# XL_N76E003K2__MAIN.net
KiCad netlist of a schematic drawn in Altium Designer
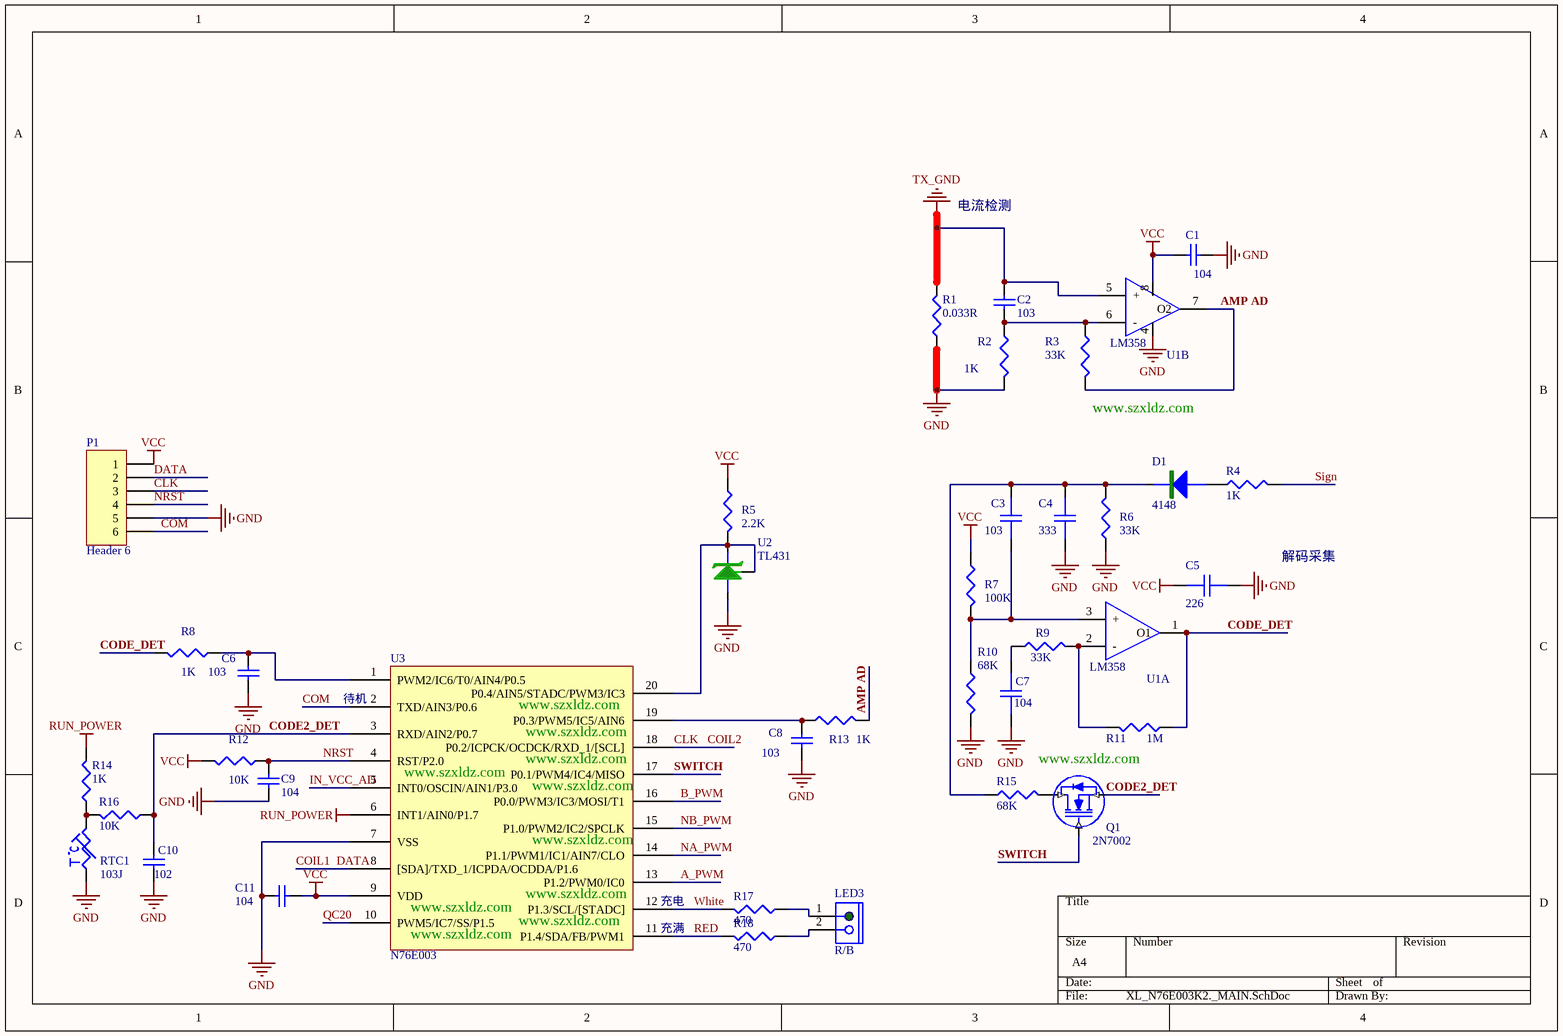
[diagram p0: XL_N76E003K2._MAIN.SchDoc]

(export (version "E")
  (design (tool "Eeschema 10.0.6"))
  (components
    (comp (ref "C1")
      (value "104")
      (footprint "C0402")
      (description "Capacitor")
      (fields (field (name "PUBLISHER") "Altium Limited"))
      (libsource (lib "*") (part "Cap"))
    )
    (comp (ref "C2")
      (value "103")
      (footprint "C0402")
      (description "Capacitor")
      (fields (field (name "PUBLISHER") "Altium Limited"))
      (libsource (lib "*") (part "Cap"))
    )
    (comp (ref "C3") (value "103") (footprint "C0402") (libsource (lib "*") (part "CH")))
    (comp (ref "C4") (value "333") (footprint "C0402") (libsource (lib "*") (part "CH")))
    (comp (ref "C5") (value "226") (footprint "C0805") (libsource (lib "*") (part "CH")))
    (comp (ref "C6")
      (value "103")
      (footprint "C0402")
      (description "Capacitor")
      (fields (field (name "PUBLISHER") "Altium Limited"))
      (libsource (lib "*") (part "Cap"))
    )
    (comp (ref "C7") (value "104") (footprint "C0402") (libsource (lib "*") (part "CH")))
    (comp (ref "C8")
      (value "103")
      (footprint "C0402")
      (description "Capacitor")
      (fields (field (name "PUBLISHER") "Altium Limited"))
      (libsource (lib "*") (part "Cap"))
    )
    (comp (ref "C9")
      (value "104")
      (footprint "C0402")
      (description "Capacitor")
      (fields (field (name "PUBLISHER") "Altium Limited"))
      (libsource (lib "*") (part "Cap"))
    )
    (comp (ref "C10")
      (value "102")
      (footprint "C0402")
      (description "Capacitor")
      (fields (field (name "PUBLISHER") "Altium Limited"))
      (libsource (lib "*") (part "Cap"))
    )
    (comp (ref "C11")
      (value "104")
      (footprint "C0402")
      (description "Capacitor")
      (fields (field (name "PUBLISHER") "Altium Limited"))
      (libsource (lib "*") (part "Cap"))
    )
    (comp (ref "D1")
      (value "4148")
      (footprint "sod323")
      (description "1N4001")
      (libsource (lib "*") (part "D0"))
    )
    (comp (ref "LED3") (value "R/B") (footprint "PIN2_2.54") (libsource (lib "Xin Lang") (part "CON2")))
    (comp (ref "P1")
      (value "Header 6")
      (footprint "SPIN6")
      (description "Header, 6-Pin")
      (fields (field (name "PUBLISHER") "Altium Limited"))
      (libsource (lib "Miscellaneous Connectors") (part "Header 6"))
    )
    (comp (ref "Q1") (value "2N7002") (footprint "SOT-23B") (libsource (lib "lxzschlib") (part "MOSFETN")))
    (comp (ref "R1") (value "0.033R") (footprint "R0805") (description "1K") (libsource (lib "*") (part "R")))
    (comp (ref "R2") (value "1K") (footprint "R0402") (libsource (lib "*") (part "R")))
    (comp (ref "R3") (value "33K") (footprint "R0402") (description "1K") (libsource (lib "*") (part "R")))
    (comp (ref "R4") (value "1K") (footprint "R0402") (libsource (lib "*") (part "R")))
    (comp (ref "R5") (value "2.2K") (footprint "R0402") (description "1K") (libsource (lib "*") (part "R")))
    (comp (ref "R6") (value "33K") (footprint "R0402") (description "1K") (libsource (lib "*") (part "R")))
    (comp (ref "R7") (value "100K") (footprint "R0402") (description "1K") (libsource (lib "*") (part "R")))
    (comp (ref "R8") (value "1K") (footprint "R0402") (libsource (lib "*") (part "R")))
    (comp (ref "R9") (value "33K") (footprint "R0402") (description "1K") (libsource (lib "*") (part "R")))
    (comp (ref "R10") (value "68K") (footprint "R0402") (description "1K") (libsource (lib "*") (part "R")))
    (comp (ref "R11") (value "1M") (footprint "R0402") (description "1K") (libsource (lib "*") (part "R")))
    (comp (ref "R12") (value "10K") (footprint "R0402") (libsource (lib "*") (part "R")))
    (comp (ref "R13") (value "1K") (footprint "R0402") (libsource (lib "*") (part "R")))
    (comp (ref "R14") (value "1K") (footprint "R0402") (libsource (lib "lxzschlib") (part "R")))
    (comp (ref "R15") (value "68K") (footprint "R0402") (description "1K") (libsource (lib "*") (part "R")))
    (comp (ref "R16")
      (value "10K")
      (footprint "R0402")
      (description "1K")
      (libsource (lib "lxzschlib") (part "R"))
    )
    (comp (ref "R17") (value "470") (footprint "R0402") (description "1K") (libsource (lib "") (part "R_1")))
    (comp (ref "R18") (value "470") (footprint "R0402") (description "1K") (libsource (lib "") (part "R_1")))
    (comp (ref "RTC1") (value "103J") (footprint "R0402") (libsource (lib "lxzschlib") (part "RTC")))
    (comp (ref "U1") (value "LM358") (footprint "SOP8") (libsource (lib "lxzschlib") (part "4558")))
    (comp (ref "U2")
      (value "TL431")
      (footprint "SOT-23-431")
      (description "IC")
      (libsource (lib "lxzschlib") (part "IC TL431"))
    )
    (comp (ref "U3") (value "N76E003") (footprint "SOP20") (libsource (lib "BEE802_V11") (part "103F")))
  )
  (nets
    (net (code "1") (name "/AMP AD") (class "Default")
      (node (ref "R13") (pin "2") (pintype "passive"))
      (node (ref "R3") (pin "2") (pintype "passive"))
      (node (ref "U1") (pin "7") (pinfunction "O2_7") (pintype "passive"))
    )
    (net (code "2") (name "/A_PWM") (class "Default")
      (node (ref "U3") (pin "13") (pinfunction "P1.2/PWM0/IC0_13") (pintype "passive"))
    )
    (net (code "3") (name "/B_PWM") (class "Default")
      (node (ref "U3") (pin "16") (pinfunction "P0.0/PWM3/IC3/MOSI/T1_16") (pintype "passive"))
    )
    (net (code "4") (name "/CLK") (class "Default")
      (node (ref "P1") (pin "3") (pinfunction "3_3") (pintype "passive"))
      (node (ref "U3") (pin "18") (pinfunction "P0.2/ICPCK/OCDCK/RXD_1/[SCL]_18") (pintype "passive"))
    )
    (net (code "5") (name "/CODE2_DET") (class "Default")
      (node (ref "C10") (pin "2") (pinfunction "2_2") (pintype "passive"))
      (node (ref "Q1") (pin "E") (pinfunction "S_E") (pintype "input"))
      (node (ref "R16") (pin "1") (pintype "passive"))
      (node (ref "U3") (pin "3") (pinfunction "RXD/AIN2/P0.7_3") (pintype "passive"))
    )
    (net (code "6") (name "/CODE_DET") (class "Default")
      (node (ref "R11") (pin "1") (pintype "passive"))
      (node (ref "R8") (pin "2") (pintype "passive"))
      (node (ref "U1") (pin "1") (pinfunction "O1_1") (pintype "passive"))
    )
    (net (code "7") (name "/COIL1") (class "Default")
      (node (ref "P1") (pin "2") (pinfunction "2_2") (pintype "passive"))
      (node (ref "U3") (pin "8") (pinfunction "[SDA]/TXD_1/ICPDA/OCDDA/P1.6_8") (pintype "passive"))
    )
    (net (code "8") (name "/COM") (class "Default")
      (node (ref "P1") (pin "6") (pinfunction "6_6") (pintype "passive"))
      (node (ref "U3") (pin "2") (pinfunction "TXD/AIN3/P0.6_2") (pintype "passive"))
    )
    (net (code "9") (name "/IN_VCC_AD") (class "Default")
      (node (ref "U3") (pin "5") (pinfunction "INT0/OSCIN/AIN1/P3.0_5") (pintype "passive"))
    )
    (net (code "10") (name "/NA_PWM") (class "Default")
      (node (ref "U3") (pin "14") (pinfunction "P1.1/PWM1/IC1/AIN7/CLO_14") (pintype "passive"))
    )
    (net (code "11") (name "/NB_PWM") (class "Default")
      (node (ref "U3") (pin "15") (pinfunction "P1.0/PWM2/IC2/SPCLK_15") (pintype "passive"))
    )
    (net (code "12") (name "/NRST") (class "Default")
      (node (ref "C9") (pin "1") (pinfunction "1_1") (pintype "passive"))
      (node (ref "P1") (pin "4") (pinfunction "4_4") (pintype "passive"))
      (node (ref "R12") (pin "1") (pintype "passive"))
      (node (ref "U3") (pin "4") (pinfunction "RST/P2.0_4") (pintype "passive"))
    )
    (net (code "13") (name "/QC20") (class "Default")
      (node (ref "U3") (pin "10") (pinfunction "PWM5/IC7/SS/P1.5_10") (pintype "passive"))
    )
    (net (code "14") (name "/RED") (class "Default")
      (node (ref "R18") (pin "1") (pintype "passive"))
      (node (ref "U3") (pin "11") (pinfunction "P1.4/SDA/FB/PWM1_11") (pintype "passive"))
    )
    (net (code "15") (name "/SWITCH") (class "Default")
      (node (ref "Q1") (pin "B") (pinfunction "G_B") (pintype "input"))
      (node (ref "U3") (pin "17") (pinfunction "P0.1/PWM4/IC4/MISO_17") (pintype "passive"))
    )
    (net (code "16") (name "/Sign") (class "Default") (node (ref "R4") (pin "2") (pintype "passive")))
    (net (code "17") (name "/White") (class "Default")
      (node (ref "R17") (pin "1") (pintype "passive"))
      (node (ref "U3") (pin "12") (pinfunction "P1.3/SCL/[STADC]_12") (pintype "passive"))
    )
    (net (code "18") (name "GND") (class "Default")
      (node (ref "C1") (pin "1") (pinfunction "1_1") (pintype "passive"))
      (node (ref "C10") (pin "1") (pinfunction "1_1") (pintype "passive"))
      (node (ref "C11") (pin "1") (pinfunction "1_1") (pintype "passive"))
      (node (ref "C4") (pin "1") (pintype "passive"))
      (node (ref "C5") (pin "1") (pintype "passive"))
      (node (ref "C6") (pin "1") (pinfunction "1_1") (pintype "passive"))
      (node (ref "C7") (pin "1") (pintype "passive"))
      (node (ref "C8") (pin "2") (pinfunction "2_2") (pintype "passive"))
      (node (ref "C9") (pin "2") (pinfunction "2_2") (pintype "passive"))
      (node (ref "P1") (pin "5") (pinfunction "5_5") (pintype "passive"))
      (node (ref "R1") (pin "1") (pintype "passive"))
      (node (ref "R10") (pin "2") (pintype "passive"))
      (node (ref "R2") (pin "2") (pintype "passive"))
      (node (ref "R6") (pin "1") (pintype "passive"))
      (node (ref "RTC1") (pin "1") (pintype "passive"))
      (node (ref "U1") (pin "4") (pintype "passive"))
      (node (ref "U2") (pin "1") (pintype "passive"))
      (node (ref "U3") (pin "7") (pinfunction "VSS_7") (pintype "passive"))
    )
    (net (code "19") (name "Net-(C3-Pad1)") (class "Default")
      (node (ref "C3") (pin "1") (pintype "passive"))
      (node (ref "C4") (pin "2") (pintype "passive"))
      (node (ref "D1") (pin "2") (pintype "passive"))
      (node (ref "R15") (pin "1") (pintype "passive"))
      (node (ref "R6") (pin "2") (pintype "passive"))
    )
    (net (code "20") (name "Net-(C7-Pad2)") (class "Default")
      (node (ref "C7") (pin "2") (pintype "passive"))
      (node (ref "R9") (pin "1") (pintype "passive"))
    )
    (net (code "21") (name "Net-(D1-Pad1)") (class "Default")
      (node (ref "D1") (pin "1") (pintype "passive"))
      (node (ref "R4") (pin "1") (pintype "passive"))
    )
    (net (code "22") (name "Net-(LED3-Pad1)") (class "Default")
      (node (ref "LED3") (pin "1") (pintype "passive"))
      (node (ref "R17") (pin "2") (pintype "passive"))
    )
    (net (code "23") (name "Net-(LED3-Pad2)") (class "Default")
      (node (ref "LED3") (pin "2") (pintype "passive"))
      (node (ref "R18") (pin "2") (pintype "passive"))
    )
    (net (code "24") (name "Net-(Q1-D)") (class "Default")
      (node (ref "Q1") (pin "C") (pinfunction "D_C") (pintype "input"))
      (node (ref "R15") (pin "2") (pintype "passive"))
    )
    (net (code "25") (name "Net-(R14-Pad1)") (class "Default")
      (node (ref "R14") (pin "1") (pintype "passive"))
      (node (ref "R16") (pin "2") (pintype "passive"))
      (node (ref "RTC1") (pin "2") (pintype "passive"))
    )
    (net (code "26") (name "Net-(U1A-+)") (class "Default")
      (node (ref "C3") (pin "2") (pintype "passive"))
      (node (ref "R10") (pin "1") (pintype "passive"))
      (node (ref "R7") (pin "2") (pintype "passive"))
      (node (ref "U1") (pin "3") (pinfunction "+_3") (pintype "passive"))
    )
    (net (code "27") (name "Net-(U1A--)") (class "Default")
      (node (ref "R11") (pin "2") (pintype "passive"))
      (node (ref "R9") (pin "2") (pintype "passive"))
      (node (ref "U1") (pin "2") (pinfunction "-_2") (pintype "passive"))
    )
    (net (code "28") (name "Net-(U1B--)") (class "Default")
      (node (ref "C2") (pin "2") (pinfunction "2_2") (pintype "passive"))
      (node (ref "R2") (pin "1") (pintype "passive"))
      (node (ref "R3") (pin "1") (pintype "passive"))
      (node (ref "U1") (pin "6") (pinfunction "-_6") (pintype "passive"))
    )
    (net (code "29") (name "Net-(U3-P0.3{slash}PWM5{slash}IC5{slash}AIN6)") (class "Default")
      (node (ref "C8") (pin "1") (pinfunction "1_1") (pintype "passive"))
      (node (ref "R13") (pin "1") (pintype "passive"))
      (node (ref "U3") (pin "19") (pinfunction "P0.3/PWM5/IC5/AIN6_19") (pintype "passive"))
    )
    (net (code "30") (name "Net-(U3-P0.4{slash}AIN5{slash}STADC{slash}PWM3{slash}IC3)") (class "Default")
      (node (ref "R5") (pin "2") (pintype "passive"))
      (node (ref "U2") (pin "2") (pintype "passive"))
      (node (ref "U2") (pin "3") (pintype "passive"))
      (node (ref "U3") (pin "20") (pinfunction "P0.4/AIN5/STADC/PWM3/IC3_20") (pintype "passive"))
    )
    (net (code "31") (name "Net-(U3-PWM2{slash}IC6{slash}T0{slash}AIN4{slash}P0.5)") (class "Default")
      (node (ref "C6") (pin "2") (pinfunction "2_2") (pintype "passive"))
      (node (ref "R8") (pin "1") (pintype "passive"))
      (node (ref "U3") (pin "1") (pinfunction "PWM2/IC6/T0/AIN4/P0.5_1") (pintype "passive"))
    )
    (net (code "32") (name "RUN_POWER") (class "Default")
      (node (ref "R14") (pin "2") (pintype "passive"))
      (node (ref "U3") (pin "6") (pinfunction "INT1/AIN0/P1.7_6") (pintype "passive"))
    )
    (net (code "33") (name "TX_GND") (class "Default")
      (node (ref "C2") (pin "1") (pinfunction "1_1") (pintype "passive"))
      (node (ref "R1") (pin "2") (pintype "passive"))
      (node (ref "U1") (pin "5") (pinfunction "+_5") (pintype "passive"))
    )
    (net (code "34") (name "VCC") (class "Default")
      (node (ref "C1") (pin "2") (pinfunction "2_2") (pintype "passive"))
      (node (ref "C11") (pin "2") (pinfunction "2_2") (pintype "passive"))
      (node (ref "C5") (pin "2") (pintype "passive"))
      (node (ref "P1") (pin "1") (pinfunction "1_1") (pintype "passive"))
      (node (ref "R12") (pin "2") (pintype "passive"))
      (node (ref "R5") (pin "1") (pintype "passive"))
      (node (ref "R7") (pin "1") (pintype "passive"))
      (node (ref "U1") (pin "8") (pintype "passive"))
      (node (ref "U3") (pin "9") (pinfunction "VDD_9") (pintype "passive"))
    )
  )
)
